# motherboard_v1_21.net
KiCad netlist of a schematic drawn in EAGLE
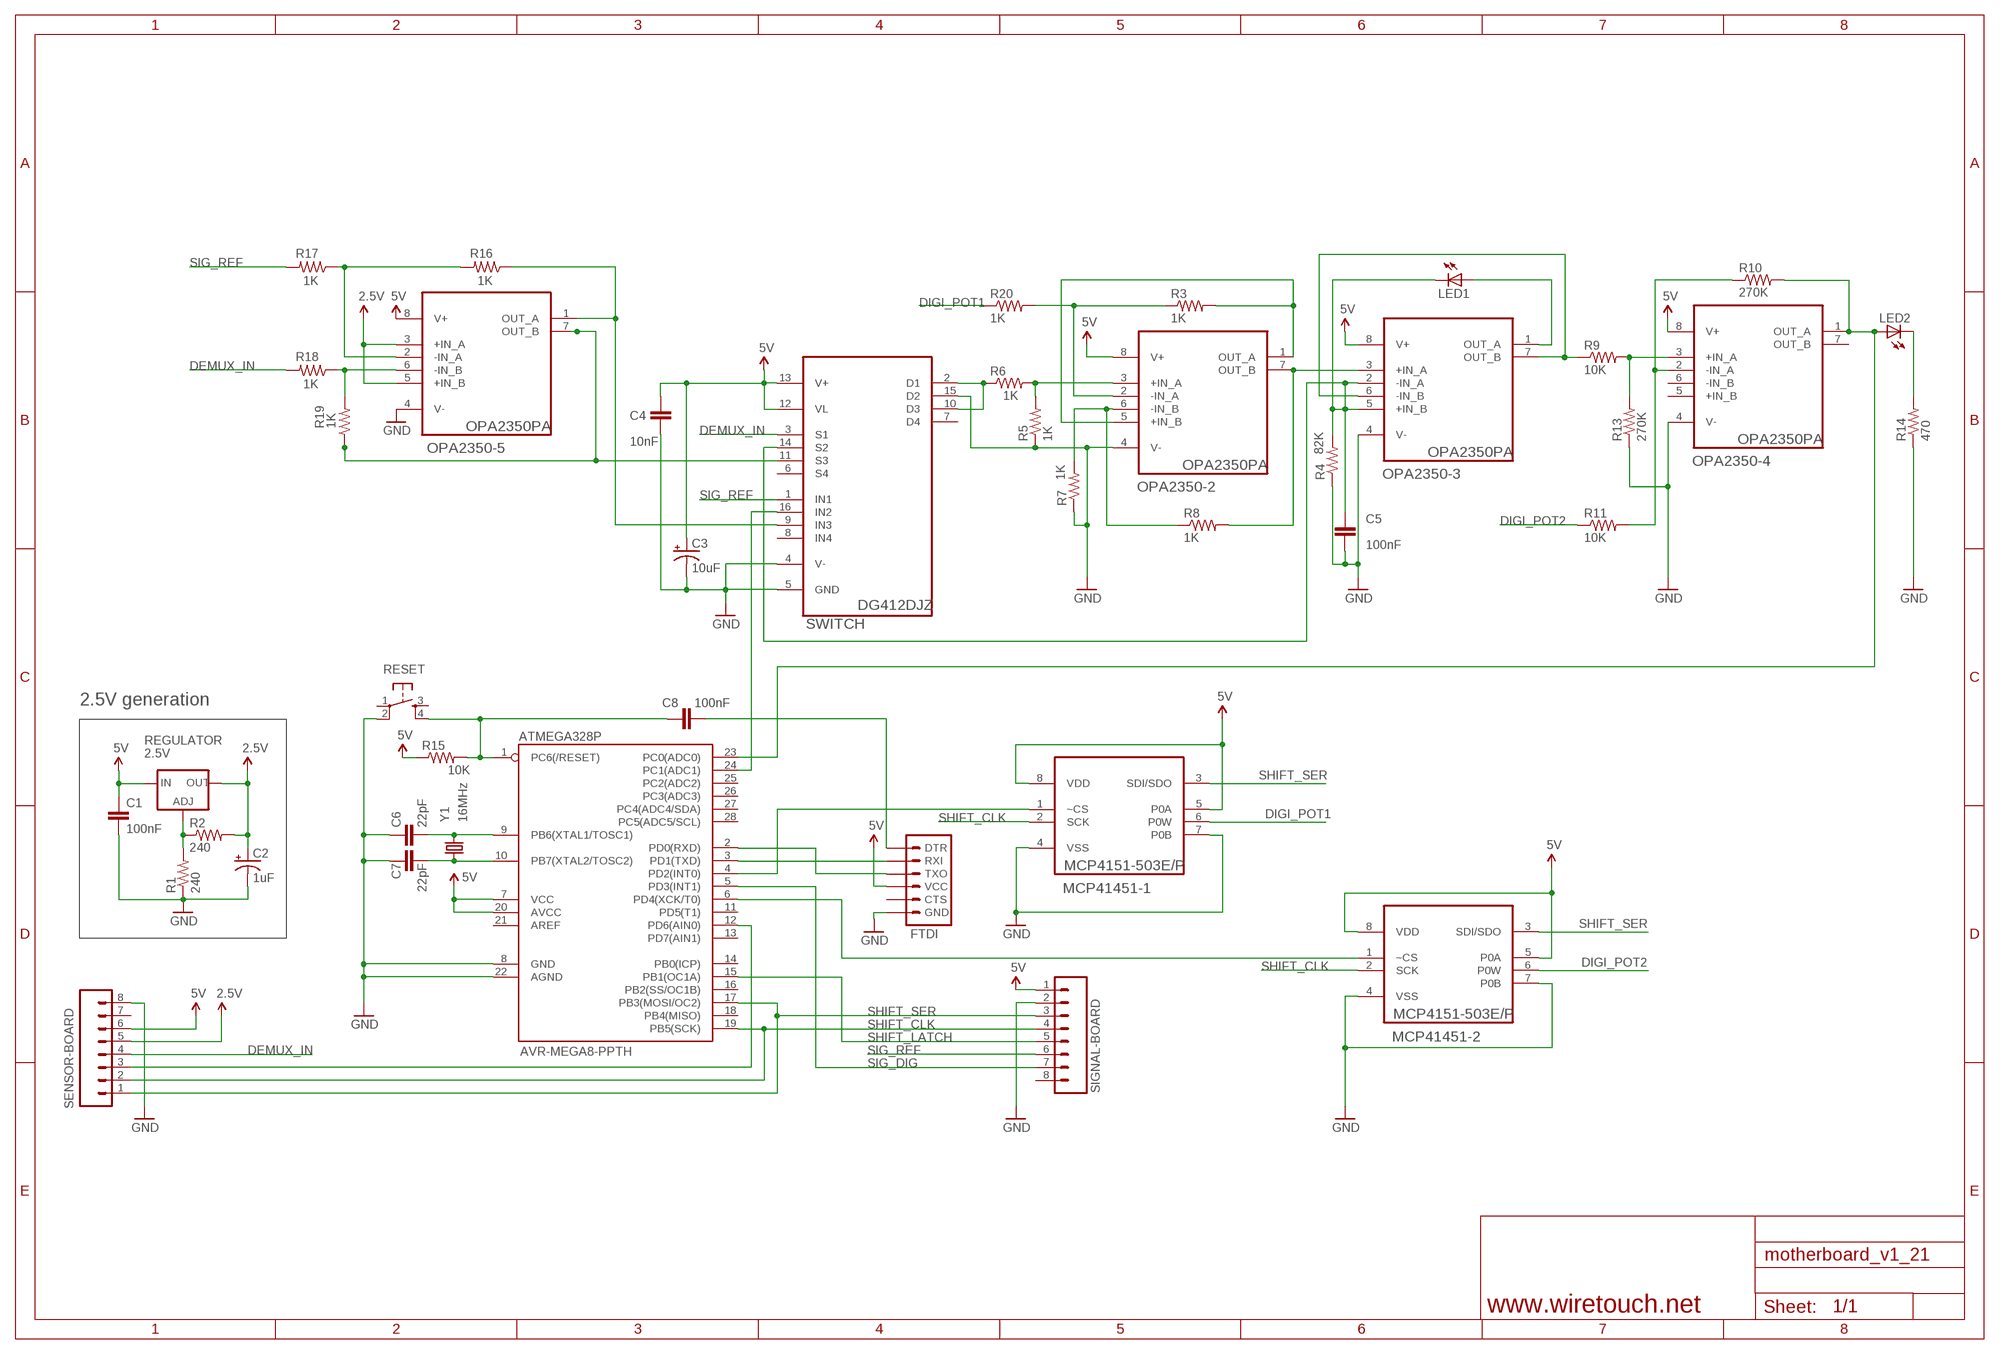
[diagram p0: schematic, sheet 1]

(export (version "E")
  (design (tool "Eeschema 10.0.6"))
  (components
    (comp (ref "ATMEGA328P")
      (value "AVR-MEGA8-PPTH")
      (footprint "eagle-import:DIL28-3")
      (libsource (lib "eagle-import") (part "AVR-MEGA8-PPTH"))
    )
    (comp (ref "C1")
      (value "100nF")
      (footprint "eagle-import:CAP-PTH-SMALL")
      (libsource (lib "eagle-import") (part "CAPPTH"))
    )
    (comp (ref "C2")
      (value "1uF")
      (footprint "eagle-import:CPOL-RADIAL-10UF-25V")
      (libsource (lib "eagle-import") (part "CAP_POLPTH2"))
    )
    (comp (ref "C3")
      (value "10uF")
      (footprint "eagle-import:CPOL-RADIAL-10UF-25V")
      (libsource (lib "eagle-import") (part "CAP_POLPTH2"))
    )
    (comp (ref "C4")
      (value "10nF")
      (footprint "eagle-import:CAP-PTH-SMALL")
      (libsource (lib "eagle-import") (part "CAPPTH"))
    )
    (comp (ref "C5")
      (value "100nF")
      (footprint "eagle-import:CAP-PTH-SMALL")
      (libsource (lib "eagle-import") (part "CAPPTH"))
    )
    (comp (ref "C6")
      (value "22pF")
      (footprint "eagle-import:CAP-PTH-SMALL2")
      (libsource (lib "eagle-import") (part "CAPPTH2"))
    )
    (comp (ref "C7")
      (value "22pF")
      (footprint "eagle-import:CAP-PTH-SMALL2")
      (libsource (lib "eagle-import") (part "CAPPTH2"))
    )
    (comp (ref "C8")
      (value "100nF")
      (footprint "eagle-import:CAP-PTH-SMALL2")
      (libsource (lib "eagle-import") (part "CAPPTH2"))
    )
    (comp (ref "FTDI")
      (value "ARDUINO_SERIAL_PROGRAMLONGPADS")
      (footprint "eagle-import:1X06_LONGPADS")
      (libsource (lib "eagle-import") (part "ARDUINO_SERIAL_PROGRAMLONGPADS"))
    )
    (comp (ref "LED1")
      (value "LED3MM")
      (footprint "eagle-import:LED3MM")
      (libsource (lib "eagle-import") (part "LED3MM"))
    )
    (comp (ref "LED2")
      (value "LED5MM")
      (footprint "eagle-import:LED5MM")
      (libsource (lib "eagle-import") (part "LED5MM"))
    )
    (comp (ref "MCP41451-1")
      (value "MCP4151-503E/P")
      (footprint "eagle-import:DIP254P762X533-8")
      (libsource (lib "eagle-import") (part "MCP4151-503E/P"))
    )
    (comp (ref "MCP41451-2")
      (value "MCP4151-503E/P")
      (footprint "eagle-import:DIP254P762X533-8")
      (libsource (lib "eagle-import") (part "MCP4151-503E/P"))
    )
    (comp (ref "OPA2350-2")
      (value "OPA2350PA")
      (footprint "eagle-import:DIP254P762X508-8")
      (libsource (lib "eagle-import") (part "OPA2350PA"))
    )
    (comp (ref "OPA2350-3")
      (value "OPA2350PA")
      (footprint "eagle-import:DIP254P762X508-8")
      (libsource (lib "eagle-import") (part "OPA2350PA"))
    )
    (comp (ref "OPA2350-4")
      (value "OPA2350PA")
      (footprint "eagle-import:DIP254P762X508-8")
      (libsource (lib "eagle-import") (part "OPA2350PA"))
    )
    (comp (ref "OPA2350-5")
      (value "OPA2350PA")
      (footprint "eagle-import:DIP254P762X508-8")
      (libsource (lib "eagle-import") (part "OPA2350PA"))
    )
    (comp (ref "R1")
      (value "240")
      (footprint "eagle-import:AXIAL-0.3")
      (libsource (lib "eagle-import") (part "RESISTORAXIAL-0.3"))
    )
    (comp (ref "R2")
      (value "240")
      (footprint "eagle-import:AXIAL-0.3")
      (libsource (lib "eagle-import") (part "RESISTORAXIAL-0.3"))
    )
    (comp (ref "R3")
      (value "1K")
      (footprint "eagle-import:AXIAL-0.3")
      (libsource (lib "eagle-import") (part "RESISTORAXIAL-0.3"))
    )
    (comp (ref "R4")
      (value "82K")
      (footprint "eagle-import:AXIAL-0.3")
      (libsource (lib "eagle-import") (part "RESISTORAXIAL-0.3"))
    )
    (comp (ref "R5")
      (value "1K")
      (footprint "eagle-import:AXIAL-0.3")
      (libsource (lib "eagle-import") (part "RESISTORAXIAL-0.3"))
    )
    (comp (ref "R6")
      (value "1K")
      (footprint "eagle-import:AXIAL-0.3")
      (libsource (lib "eagle-import") (part "RESISTORAXIAL-0.3"))
    )
    (comp (ref "R7")
      (value "1K")
      (footprint "eagle-import:AXIAL-0.3")
      (libsource (lib "eagle-import") (part "RESISTORAXIAL-0.3"))
    )
    (comp (ref "R8")
      (value "1K")
      (footprint "eagle-import:AXIAL-0.3")
      (libsource (lib "eagle-import") (part "RESISTORAXIAL-0.3"))
    )
    (comp (ref "R9")
      (value "10K")
      (footprint "eagle-import:AXIAL-0.3")
      (libsource (lib "eagle-import") (part "RESISTORAXIAL-0.3"))
    )
    (comp (ref "R10")
      (value "270K")
      (footprint "eagle-import:AXIAL-0.3")
      (libsource (lib "eagle-import") (part "RESISTORAXIAL-0.3"))
    )
    (comp (ref "R11")
      (value "10K")
      (footprint "eagle-import:AXIAL-0.3")
      (libsource (lib "eagle-import") (part "RESISTORAXIAL-0.3"))
    )
    (comp (ref "R13")
      (value "270K")
      (footprint "eagle-import:AXIAL-0.3")
      (libsource (lib "eagle-import") (part "RESISTORAXIAL-0.3"))
    )
    (comp (ref "R14")
      (value "470")
      (footprint "eagle-import:AXIAL-0.3")
      (libsource (lib "eagle-import") (part "RESISTORAXIAL-0.3"))
    )
    (comp (ref "R15")
      (value "10K")
      (footprint "eagle-import:AXIAL-0.3")
      (libsource (lib "eagle-import") (part "RESISTORAXIAL-0.3"))
    )
    (comp (ref "R16")
      (value "1K")
      (footprint "eagle-import:AXIAL-0.3")
      (libsource (lib "eagle-import") (part "RESISTORAXIAL-0.3"))
    )
    (comp (ref "R17")
      (value "1K")
      (footprint "eagle-import:AXIAL-0.3")
      (libsource (lib "eagle-import") (part "RESISTORAXIAL-0.3"))
    )
    (comp (ref "R18")
      (value "1K")
      (footprint "eagle-import:AXIAL-0.3")
      (libsource (lib "eagle-import") (part "RESISTORAXIAL-0.3"))
    )
    (comp (ref "R19")
      (value "1K")
      (footprint "eagle-import:AXIAL-0.3")
      (libsource (lib "eagle-import") (part "RESISTORAXIAL-0.3"))
    )
    (comp (ref "R20")
      (value "1K")
      (footprint "eagle-import:AXIAL-0.3")
      (libsource (lib "eagle-import") (part "RESISTORAXIAL-0.3"))
    )
    (comp (ref "REGULATOR")
      (value "2.5V")
      (footprint "eagle-import:TO220-ADJ")
      (libsource (lib "eagle-import") (part "V_REG_317SINK"))
    )
    (comp (ref "RESET")
      (value "TAC_SWITCHPTH")
      (footprint "eagle-import:TACTILE-PTH")
      (libsource (lib "eagle-import") (part "TAC_SWITCHPTH"))
    )
    (comp (ref "SENSOR-BOARD")
      (value "M08LONGPADS")
      (footprint "eagle-import:1X08_LONGPADS")
      (libsource (lib "eagle-import") (part "M08LONGPADS"))
    )
    (comp (ref "SIGNAL-BOARD")
      (value "M08LONGPADS")
      (footprint "eagle-import:1X08_LONGPADS")
      (libsource (lib "eagle-import") (part "M08LONGPADS"))
    )
    (comp (ref "SWITCH")
      (value "DG412DJZ")
      (footprint "eagle-import:DIP254P762X533-16")
      (libsource (lib "eagle-import") (part "DG412DJZ"))
    )
    (comp (ref "Y1")
      (value "16MHz")
      (footprint "eagle-import:HC49US")
      (libsource (lib "eagle-import") (part "CRYSTALHC49US"))
    )
  )
  (nets
    (net (code "1") (name "/DEMUX_IN") (class "Default")
      (node (ref "R18") (pin "P$2") (pinfunction "2_P$2") (pintype "passive"))
      (node (ref "SENSOR-BOARD") (pin "4") (pinfunction "4_4") (pintype "passive"))
      (node (ref "SWITCH") (pin "3") (pinfunction "S1_3") (pintype "input"))
    )
    (net (code "2") (name "/DIGI_POT1") (class "Default")
      (node (ref "MCP41451-1") (pin "6") (pinfunction "P0W_6") (pintype "passive"))
      (node (ref "R20") (pin "P$1") (pinfunction "1_P$1") (pintype "passive"))
    )
    (net (code "3") (name "/DIGI_POT2") (class "Default")
      (node (ref "MCP41451-2") (pin "6") (pinfunction "P0W_6") (pintype "passive"))
      (node (ref "R11") (pin "P$1") (pinfunction "1_P$1") (pintype "passive"))
    )
    (net (code "4") (name "/SHIFT_CLK") (class "Default")
      (node (ref "ATMEGA328P") (pin "19") (pinfunction "PB5(SCK)_19") (pintype "bidirectional"))
      (node (ref "MCP41451-1") (pin "2") (pinfunction "SCK_2") (pintype "input"))
      (node (ref "MCP41451-2") (pin "2") (pinfunction "SCK_2") (pintype "input"))
      (node (ref "SENSOR-BOARD") (pin "2") (pinfunction "2_2") (pintype "passive"))
      (node (ref "SIGNAL-BOARD") (pin "4") (pinfunction "4_4") (pintype "passive"))
    )
    (net (code "5") (name "/SHIFT_LATCH") (class "Default")
      (node (ref "ATMEGA328P") (pin "15") (pinfunction "PB1(OC1A)_15") (pintype "bidirectional"))
      (node (ref "SIGNAL-BOARD") (pin "5") (pinfunction "5_5") (pintype "passive"))
    )
    (net (code "6") (name "/SHIFT_SER") (class "Default")
      (node (ref "ATMEGA328P") (pin "17") (pinfunction "PB3(MOSI/OC2)_17") (pintype "bidirectional"))
      (node (ref "MCP41451-1") (pin "3") (pinfunction "SDI/SDO_3") (pintype "bidirectional"))
      (node (ref "MCP41451-2") (pin "3") (pinfunction "SDI/SDO_3") (pintype "bidirectional"))
      (node (ref "SENSOR-BOARD") (pin "1") (pinfunction "1_1") (pintype "passive"))
      (node (ref "SIGNAL-BOARD") (pin "3") (pinfunction "3_3") (pintype "passive"))
    )
    (net (code "7") (name "/SIG_DIG") (class "Default")
      (node (ref "ATMEGA328P") (pin "5") (pinfunction "PD3(INT1)_5") (pintype "bidirectional"))
      (node (ref "SIGNAL-BOARD") (pin "7") (pinfunction "7_7") (pintype "passive"))
    )
    (net (code "8") (name "/SIG_REF") (class "Default")
      (node (ref "R17") (pin "P$2") (pinfunction "2_P$2") (pintype "passive"))
      (node (ref "SIGNAL-BOARD") (pin "6") (pinfunction "6_6") (pintype "passive"))
      (node (ref "SWITCH") (pin "1") (pinfunction "IN1_1") (pintype "input"))
    )
    (net (code "9") (name "2.5V") (class "Default")
      (node (ref "C2") (pin "1") (pinfunction "+_1") (pintype "passive"))
      (node (ref "OPA2350-5") (pin "3") (pinfunction "+IN_A_3") (pintype "input"))
      (node (ref "OPA2350-5") (pin "5") (pinfunction "+IN_B_5") (pintype "input"))
      (node (ref "R2") (pin "P$2") (pinfunction "2_P$2") (pintype "passive"))
      (node (ref "REGULATOR") (pin "OUT") (pinfunction "OUT_OUT") (pintype "output"))
      (node (ref "SENSOR-BOARD") (pin "5") (pinfunction "5_5") (pintype "passive"))
    )
    (net (code "10") (name "5V") (class "Default")
      (node (ref "ATMEGA328P") (pin "20") (pinfunction "AVCC_20") (pintype "bidirectional"))
      (node (ref "ATMEGA328P") (pin "7") (pinfunction "VCC_7") (pintype "bidirectional"))
      (node (ref "C1") (pin "1") (pinfunction "1_1") (pintype "passive"))
      (node (ref "C3") (pin "1") (pinfunction "+_1") (pintype "passive"))
      (node (ref "C4") (pin "1") (pinfunction "1_1") (pintype "passive"))
      (node (ref "FTDI") (pin "4") (pinfunction "VCC_4") (pintype "passive"))
      (node (ref "MCP41451-1") (pin "5") (pinfunction "P0A_5") (pintype "passive"))
      (node (ref "MCP41451-1") (pin "8") (pinfunction "VDD_8") (pintype "power_in"))
      (node (ref "MCP41451-2") (pin "5") (pinfunction "P0A_5") (pintype "passive"))
      (node (ref "MCP41451-2") (pin "8") (pinfunction "VDD_8") (pintype "power_in"))
      (node (ref "OPA2350-2") (pin "8") (pinfunction "V+_8") (pintype "power_in"))
      (node (ref "OPA2350-3") (pin "8") (pinfunction "V+_8") (pintype "power_in"))
      (node (ref "OPA2350-4") (pin "8") (pinfunction "V+_8") (pintype "power_in"))
      (node (ref "OPA2350-5") (pin "8") (pinfunction "V+_8") (pintype "power_in"))
      (node (ref "R15") (pin "P$1") (pinfunction "1_P$1") (pintype "passive"))
      (node (ref "REGULATOR") (pin "IN") (pinfunction "IN_IN") (pintype "input"))
      (node (ref "SENSOR-BOARD") (pin "6") (pinfunction "6_6") (pintype "passive"))
      (node (ref "SIGNAL-BOARD") (pin "1") (pinfunction "1_1") (pintype "passive"))
      (node (ref "SWITCH") (pin "12") (pinfunction "VL_12") (pintype "power_in"))
      (node (ref "SWITCH") (pin "13") (pinfunction "V+_13") (pintype "power_in"))
    )
    (net (code "11") (name "GND") (class "Default")
      (node (ref "ATMEGA328P") (pin "22") (pinfunction "AGND_22") (pintype "bidirectional"))
      (node (ref "ATMEGA328P") (pin "8") (pinfunction "GND_8") (pintype "bidirectional"))
      (node (ref "C1") (pin "2") (pinfunction "2_2") (pintype "passive"))
      (node (ref "C2") (pin "2") (pinfunction "-_2") (pintype "passive"))
      (node (ref "C3") (pin "2") (pinfunction "-_2") (pintype "passive"))
      (node (ref "C4") (pin "2") (pinfunction "2_2") (pintype "passive"))
      (node (ref "C5") (pin "2") (pinfunction "2_2") (pintype "passive"))
      (node (ref "C6") (pin "1") (pinfunction "1_1") (pintype "passive"))
      (node (ref "C7") (pin "1") (pinfunction "1_1") (pintype "passive"))
      (node (ref "FTDI") (pin "6") (pinfunction "GND_6") (pintype "passive"))
      (node (ref "MCP41451-1") (pin "4") (pinfunction "VSS_4") (pintype "power_in"))
      (node (ref "MCP41451-1") (pin "7") (pinfunction "P0B_7") (pintype "passive"))
      (node (ref "MCP41451-2") (pin "4") (pinfunction "VSS_4") (pintype "power_in"))
      (node (ref "MCP41451-2") (pin "7") (pinfunction "P0B_7") (pintype "passive"))
      (node (ref "OPA2350-2") (pin "4") (pinfunction "V-_4") (pintype "power_in"))
      (node (ref "OPA2350-3") (pin "4") (pinfunction "V-_4") (pintype "power_in"))
      (node (ref "OPA2350-4") (pin "4") (pinfunction "V-_4") (pintype "power_in"))
      (node (ref "OPA2350-5") (pin "4") (pinfunction "V-_4") (pintype "power_in"))
      (node (ref "R1") (pin "P$1") (pinfunction "1_P$1") (pintype "passive"))
      (node (ref "R13") (pin "P$1") (pinfunction "1_P$1") (pintype "passive"))
      (node (ref "R14") (pin "P$1") (pinfunction "1_P$1") (pintype "passive"))
      (node (ref "R4") (pin "P$1") (pinfunction "1_P$1") (pintype "passive"))
      (node (ref "R5") (pin "P$1") (pinfunction "1_P$1") (pintype "passive"))
      (node (ref "R7") (pin "P$1") (pinfunction "1_P$1") (pintype "passive"))
      (node (ref "RESET") (pin "2") (pinfunction "2_2") (pintype "passive"))
      (node (ref "SENSOR-BOARD") (pin "8") (pinfunction "8_8") (pintype "passive"))
      (node (ref "SIGNAL-BOARD") (pin "2") (pinfunction "2_2") (pintype "passive"))
      (node (ref "SWITCH") (pin "15") (pinfunction "D2_15") (pintype "output"))
      (node (ref "SWITCH") (pin "4") (pinfunction "V-_4") (pintype "power_in"))
      (node (ref "SWITCH") (pin "5") (pinfunction "GND_5") (pintype "passive"))
    )
    (net (code "12") (name "Net-(ATMEGA328P-PB6(XTAL1{slash}TOSC1))") (class "Default")
      (node (ref "ATMEGA328P") (pin "9") (pinfunction "PB6(XTAL1/TOSC1)_9") (pintype "bidirectional"))
      (node (ref "C6") (pin "2") (pinfunction "2_2") (pintype "passive"))
      (node (ref "Y1") (pin "2") (pinfunction "2_2") (pintype "passive"))
    )
    (net (code "13") (name "Net-(ATMEGA328P-PB7(XTAL2{slash}TOSC2))") (class "Default")
      (node (ref "ATMEGA328P") (pin "10") (pinfunction "PB7(XTAL2/TOSC2)_10") (pintype "bidirectional"))
      (node (ref "C7") (pin "2") (pinfunction "2_2") (pintype "passive"))
      (node (ref "Y1") (pin "1") (pinfunction "1_1") (pintype "passive"))
    )
    (net (code "14") (name "Net-(ATMEGA328P-PC0(ADC0))") (class "Default")
      (node (ref "ATMEGA328P") (pin "23") (pinfunction "PC0(ADC0)_23") (pintype "bidirectional"))
      (node (ref "LED2") (pin "A") (pinfunction "A_A") (pintype "passive"))
      (node (ref "OPA2350-4") (pin "1") (pinfunction "OUT_A_1") (pintype "output"))
      (node (ref "R10") (pin "P$2") (pinfunction "2_P$2") (pintype "passive"))
    )
    (net (code "15") (name "Net-(ATMEGA328P-PC1(ADC1))") (class "Default")
      (node (ref "ATMEGA328P") (pin "24") (pinfunction "PC1(ADC1)_24") (pintype "bidirectional"))
      (node (ref "SWITCH") (pin "16") (pinfunction "IN2_16") (pintype "input"))
    )
    (net (code "16") (name "Net-(ATMEGA328P-PC6({slash}RESET))") (class "Default")
      (node (ref "ATMEGA328P") (pin "1") (pinfunction "PC6(/RESET)_1") (pintype "bidirectional"))
      (node (ref "C8") (pin "1") (pinfunction "1_1") (pintype "passive"))
      (node (ref "R15") (pin "P$2") (pinfunction "2_P$2") (pintype "passive"))
      (node (ref "RESET") (pin "4") (pinfunction "4_4") (pintype "passive"))
    )
    (net (code "17") (name "Net-(ATMEGA328P-PD0(RXD))") (class "Default")
      (node (ref "ATMEGA328P") (pin "2") (pinfunction "PD0(RXD)_2") (pintype "bidirectional"))
      (node (ref "FTDI") (pin "3") (pinfunction "TXO_3") (pintype "passive"))
    )
    (net (code "18") (name "Net-(ATMEGA328P-PD1(TXD))") (class "Default")
      (node (ref "ATMEGA328P") (pin "3") (pinfunction "PD1(TXD)_3") (pintype "bidirectional"))
      (node (ref "FTDI") (pin "2") (pinfunction "RXI_2") (pintype "passive"))
    )
    (net (code "19") (name "Net-(ATMEGA328P-PD2(INT0))") (class "Default")
      (node (ref "ATMEGA328P") (pin "4") (pinfunction "PD2(INT0)_4") (pintype "bidirectional"))
      (node (ref "MCP41451-1") (pin "1") (pinfunction "~{CS}_1") (pintype "input"))
    )
    (net (code "20") (name "Net-(ATMEGA328P-PD4(XCK{slash}T0))") (class "Default")
      (node (ref "ATMEGA328P") (pin "6") (pinfunction "PD4(XCK/T0)_6") (pintype "bidirectional"))
      (node (ref "MCP41451-2") (pin "1") (pinfunction "~{CS}_1") (pintype "input"))
    )
    (net (code "21") (name "Net-(ATMEGA328P-PD6(AIN0))") (class "Default")
      (node (ref "ATMEGA328P") (pin "12") (pinfunction "PD6(AIN0)_12") (pintype "bidirectional"))
      (node (ref "SENSOR-BOARD") (pin "3") (pinfunction "3_3") (pintype "passive"))
    )
    (net (code "22") (name "Net-(FTDI-DTR)") (class "Default")
      (node (ref "C8") (pin "2") (pinfunction "2_2") (pintype "passive"))
      (node (ref "FTDI") (pin "1") (pinfunction "DTR_1") (pintype "passive"))
    )
    (net (code "23") (name "Net-(LED1-C)") (class "Default")
      (node (ref "C5") (pin "1") (pinfunction "1_1") (pintype "passive"))
      (node (ref "LED1") (pin "K") (pinfunction "C_K") (pintype "passive"))
      (node (ref "OPA2350-3") (pin "2") (pinfunction "-IN_A_2") (pintype "input"))
      (node (ref "OPA2350-3") (pin "5") (pinfunction "+IN_B_5") (pintype "input"))
      (node (ref "R4") (pin "P$2") (pinfunction "2_P$2") (pintype "passive"))
      (node (ref "SWITCH") (pin "14") (pinfunction "S2_14") (pintype "input"))
    )
    (net (code "24") (name "Net-(LED2-C)") (class "Default")
      (node (ref "LED2") (pin "K") (pinfunction "C_K") (pintype "passive"))
      (node (ref "R14") (pin "P$2") (pinfunction "2_P$2") (pintype "passive"))
    )
    (net (code "25") (name "Net-(OPA2350-2-+IN_A)") (class "Default")
      (node (ref "OPA2350-2") (pin "3") (pinfunction "+IN_A_3") (pintype "input"))
      (node (ref "R5") (pin "P$2") (pinfunction "2_P$2") (pintype "passive"))
      (node (ref "R6") (pin "P$2") (pinfunction "2_P$2") (pintype "passive"))
    )
    (net (code "26") (name "Net-(OPA2350-2-+IN_B)") (class "Default")
      (node (ref "OPA2350-2") (pin "1") (pinfunction "OUT_A_1") (pintype "output"))
      (node (ref "OPA2350-2") (pin "5") (pinfunction "+IN_B_5") (pintype "input"))
      (node (ref "R3") (pin "P$2") (pinfunction "2_P$2") (pintype "passive"))
    )
    (net (code "27") (name "Net-(OPA2350-2--IN_A)") (class "Default")
      (node (ref "OPA2350-2") (pin "2") (pinfunction "-IN_A_2") (pintype "input"))
      (node (ref "R20") (pin "P$2") (pinfunction "2_P$2") (pintype "passive"))
      (node (ref "R3") (pin "P$1") (pinfunction "1_P$1") (pintype "passive"))
    )
    (net (code "28") (name "Net-(OPA2350-2--IN_B)") (class "Default")
      (node (ref "OPA2350-2") (pin "6") (pinfunction "-IN_B_6") (pintype "input"))
      (node (ref "R7") (pin "P$2") (pinfunction "2_P$2") (pintype "passive"))
      (node (ref "R8") (pin "P$1") (pinfunction "1_P$1") (pintype "passive"))
    )
    (net (code "29") (name "Net-(OPA2350-2-OUT_B)") (class "Default")
      (node (ref "OPA2350-2") (pin "7") (pinfunction "OUT_B_7") (pintype "output"))
      (node (ref "OPA2350-3") (pin "3") (pinfunction "+IN_A_3") (pintype "input"))
      (node (ref "R8") (pin "P$2") (pinfunction "2_P$2") (pintype "passive"))
    )
    (net (code "30") (name "Net-(OPA2350-3--IN_B)") (class "Default")
      (node (ref "OPA2350-3") (pin "6") (pinfunction "-IN_B_6") (pintype "input"))
      (node (ref "OPA2350-3") (pin "7") (pinfunction "OUT_B_7") (pintype "output"))
      (node (ref "R9") (pin "P$1") (pinfunction "1_P$1") (pintype "passive"))
    )
    (net (code "31") (name "Net-(OPA2350-3-OUT_A)") (class "Default")
      (node (ref "LED1") (pin "A") (pinfunction "A_A") (pintype "passive"))
      (node (ref "OPA2350-3") (pin "1") (pinfunction "OUT_A_1") (pintype "output"))
    )
    (net (code "32") (name "Net-(OPA2350-4-+IN_A)") (class "Default")
      (node (ref "OPA2350-4") (pin "3") (pinfunction "+IN_A_3") (pintype "input"))
      (node (ref "R13") (pin "P$2") (pinfunction "2_P$2") (pintype "passive"))
      (node (ref "R9") (pin "P$2") (pinfunction "2_P$2") (pintype "passive"))
    )
    (net (code "33") (name "Net-(OPA2350-4--IN_A)") (class "Default")
      (node (ref "OPA2350-4") (pin "2") (pinfunction "-IN_A_2") (pintype "input"))
      (node (ref "R10") (pin "P$1") (pinfunction "1_P$1") (pintype "passive"))
      (node (ref "R11") (pin "P$2") (pinfunction "2_P$2") (pintype "passive"))
    )
    (net (code "34") (name "Net-(OPA2350-5--IN_A)") (class "Default")
      (node (ref "OPA2350-5") (pin "2") (pinfunction "-IN_A_2") (pintype "input"))
      (node (ref "R16") (pin "P$2") (pinfunction "2_P$2") (pintype "passive"))
      (node (ref "R17") (pin "P$1") (pinfunction "1_P$1") (pintype "passive"))
    )
    (net (code "35") (name "Net-(OPA2350-5--IN_B)") (class "Default")
      (node (ref "OPA2350-5") (pin "6") (pinfunction "-IN_B_6") (pintype "input"))
      (node (ref "R18") (pin "P$1") (pinfunction "1_P$1") (pintype "passive"))
      (node (ref "R19") (pin "P$2") (pinfunction "2_P$2") (pintype "passive"))
    )
    (net (code "36") (name "Net-(OPA2350-5-OUT_A)") (class "Default")
      (node (ref "OPA2350-5") (pin "1") (pinfunction "OUT_A_1") (pintype "output"))
      (node (ref "R16") (pin "P$1") (pinfunction "1_P$1") (pintype "passive"))
      (node (ref "SWITCH") (pin "9") (pinfunction "IN3_9") (pintype "input"))
    )
    (net (code "37") (name "Net-(OPA2350-5-OUT_B)") (class "Default")
      (node (ref "OPA2350-5") (pin "7") (pinfunction "OUT_B_7") (pintype "output"))
      (node (ref "R19") (pin "P$1") (pinfunction "1_P$1") (pintype "passive"))
      (node (ref "SWITCH") (pin "11") (pinfunction "S3_11") (pintype "input"))
    )
    (net (code "38") (name "Net-(R1-2)") (class "Default")
      (node (ref "R1") (pin "P$2") (pinfunction "2_P$2") (pintype "passive"))
      (node (ref "R2") (pin "P$1") (pinfunction "1_P$1") (pintype "passive"))
      (node (ref "REGULATOR") (pin "ADJ") (pinfunction "ADJ_ADJ") (pintype "input"))
    )
    (net (code "39") (name "Net-(R6-1)") (class "Default")
      (node (ref "R6") (pin "P$1") (pinfunction "1_P$1") (pintype "passive"))
      (node (ref "SWITCH") (pin "10") (pinfunction "D3_10") (pintype "output"))
      (node (ref "SWITCH") (pin "2") (pinfunction "D1_2") (pintype "output"))
    )
    (net (code "40") (name "unconnected-(ATMEGA328P-AREF-Pad21)") (class "Default")
      (node (ref "ATMEGA328P") (pin "21") (pinfunction "AREF_21") (pintype "bidirectional"))
    )
    (net (code "41") (name "unconnected-(ATMEGA328P-PB0(ICP)-Pad14)") (class "Default")
      (node (ref "ATMEGA328P") (pin "14") (pinfunction "PB0(ICP)_14") (pintype "bidirectional"))
    )
    (net (code "42") (name "unconnected-(ATMEGA328P-PB2(SS{slash}OC1B)-Pad16)") (class "Default")
      (node (ref "ATMEGA328P") (pin "16") (pinfunction "PB2(SS/OC1B)_16") (pintype "bidirectional"))
    )
    (net (code "43") (name "unconnected-(ATMEGA328P-PB4(MISO)-Pad18)") (class "Default")
      (node (ref "ATMEGA328P") (pin "18") (pinfunction "PB4(MISO)_18") (pintype "bidirectional"))
    )
    (net (code "44") (name "unconnected-(ATMEGA328P-PC2(ADC2)-Pad25)") (class "Default")
      (node (ref "ATMEGA328P") (pin "25") (pinfunction "PC2(ADC2)_25") (pintype "bidirectional"))
    )
    (net (code "45") (name "unconnected-(ATMEGA328P-PC3(ADC3)-Pad26)") (class "Default")
      (node (ref "ATMEGA328P") (pin "26") (pinfunction "PC3(ADC3)_26") (pintype "bidirectional"))
    )
    (net (code "46") (name "unconnected-(ATMEGA328P-PC4(ADC4{slash}SDA)-Pad27)") (class "Default")
      (node (ref "ATMEGA328P") (pin "27") (pinfunction "PC4(ADC4/SDA)_27") (pintype "bidirectional"))
    )
    (net (code "47") (name "unconnected-(ATMEGA328P-PC5(ADC5{slash}SCL)-Pad28)") (class "Default")
      (node (ref "ATMEGA328P") (pin "28") (pinfunction "PC5(ADC5/SCL)_28") (pintype "bidirectional"))
    )
    (net (code "48") (name "unconnected-(ATMEGA328P-PD5(T1)-Pad11)") (class "Default")
      (node (ref "ATMEGA328P") (pin "11") (pinfunction "PD5(T1)_11") (pintype "bidirectional"))
    )
    (net (code "49") (name "unconnected-(ATMEGA328P-PD7(AIN1)-Pad13)") (class "Default")
      (node (ref "ATMEGA328P") (pin "13") (pinfunction "PD7(AIN1)_13") (pintype "bidirectional"))
    )
    (net (code "50") (name "unconnected-(FTDI-CTS-Pad5)") (class "Default")
      (node (ref "FTDI") (pin "5") (pinfunction "CTS_5") (pintype "passive"))
    )
    (net (code "51") (name "unconnected-(OPA2350-4-+IN_B-Pad5)") (class "Default")
      (node (ref "OPA2350-4") (pin "5") (pinfunction "+IN_B_5") (pintype "input"))
    )
    (net (code "52") (name "unconnected-(OPA2350-4--IN_B-Pad6)") (class "Default")
      (node (ref "OPA2350-4") (pin "6") (pinfunction "-IN_B_6") (pintype "input"))
    )
    (net (code "53") (name "unconnected-(OPA2350-4-OUT_B-Pad7)") (class "Default")
      (node (ref "OPA2350-4") (pin "7") (pinfunction "OUT_B_7") (pintype "output"))
    )
    (net (code "54") (name "unconnected-(RESET-Pad1)") (class "Default")
      (node (ref "RESET") (pin "1") (pinfunction "1_1") (pintype "passive"))
    )
    (net (code "55") (name "unconnected-(RESET-Pad3)") (class "Default")
      (node (ref "RESET") (pin "3") (pinfunction "3_3") (pintype "passive"))
    )
    (net (code "56") (name "unconnected-(SENSOR-BOARD-Pad7)") (class "Default")
      (node (ref "SENSOR-BOARD") (pin "7") (pinfunction "7_7") (pintype "passive"))
    )
    (net (code "57") (name "unconnected-(SIGNAL-BOARD-Pad8)") (class "Default")
      (node (ref "SIGNAL-BOARD") (pin "8") (pinfunction "8_8") (pintype "passive"))
    )
    (net (code "58") (name "unconnected-(SWITCH-D4-Pad7)") (class "Default")
      (node (ref "SWITCH") (pin "7") (pinfunction "D4_7") (pintype "output"))
    )
    (net (code "59") (name "unconnected-(SWITCH-IN4-Pad8)") (class "Default")
      (node (ref "SWITCH") (pin "8") (pinfunction "IN4_8") (pintype "input"))
    )
    (net (code "60") (name "unconnected-(SWITCH-S4-Pad6)") (class "Default")
      (node (ref "SWITCH") (pin "6") (pinfunction "S4_6") (pintype "input"))
    )
  )
)
